# Strobe_blank.net
KiCad netlist of a schematic drawn in EAGLE
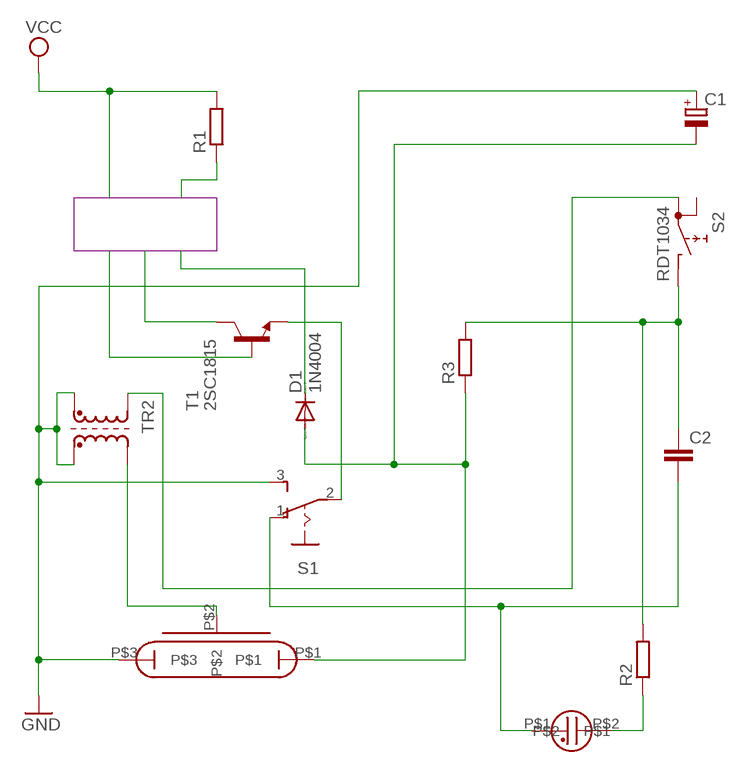
[diagram p0: schematic, sheet 1]

(export (version "E")
  (design (tool "Eeschema 10.0.6"))
  (components
    (comp (ref "C1")
      (value "CPOL-EU140CLH-0810")
      (footprint "eagle-import:140CLH-0810")
      (libsource (lib "eagle-import") (part "CPOL-EU140CLH-0810"))
    )
    (comp (ref "C2")
      (value "C-EU150-054X183")
      (footprint "eagle-import:C150-054X183")
      (libsource (lib "eagle-import") (part "C-EU150-054X183"))
    )
    (comp (ref "D1")
      (value "1N4004")
      (footprint "eagle-import:DO41-10")
      (libsource (lib "eagle-import") (part "1N4004"))
    )
    (comp (ref "R1")
      (value "R-EU_0204/2V")
      (footprint "eagle-import:0204V")
      (libsource (lib "eagle-import") (part "R-EU_0204/2V"))
    )
    (comp (ref "R2")
      (value "R-EU_0204/2V")
      (footprint "eagle-import:0204V")
      (libsource (lib "eagle-import") (part "R-EU_0204/2V"))
    )
    (comp (ref "R3")
      (value "R-EU_0204/2V")
      (footprint "eagle-import:0204V")
      (libsource (lib "eagle-import") (part "R-EU_0204/2V"))
    )
    (comp (ref "S1")
      (value "255SB")
      (footprint "eagle-import:255SB")
      (libsource (lib "eagle-import") (part "255SB"))
    )
    (comp (ref "S2")
      (value "RDT1034")
      (footprint "eagle-import:RDT1034")
      (libsource (lib "eagle-import") (part "RDT1034"))
    )
    (comp (ref "T1")
      (value "2SC1815")
      (footprint "eagle-import:TO92-ECB")
      (libsource (lib "eagle-import") (part "2SC1815"))
    )
    (comp (ref "TR2")
      (value "SM-T4")
      (footprint "eagle-import:SM-T4")
      (libsource (lib "eagle-import") (part "SM-T4"))
    )
    (comp (ref "U$1")
      (value "XENON")
      (footprint "eagle-import:XENON")
      (libsource (lib "eagle-import") (part "XENON"))
    )
    (comp (ref "U$2")
      (value "NEON")
      (footprint "eagle-import:NEON")
      (libsource (lib "eagle-import") (part "NEON"))
    )
  )
  (nets
    (net (code "1") (name "GND") (class "Default")
      (node (ref "C1") (pin "+") (pinfunction "+_+") (pintype "passive"))
      (node (ref "S1") (pin "3") (pinfunction "S_3") (pintype "passive"))
      (node (ref "TR2") (pin "2") (pinfunction "E1_2") (pintype "passive"))
      (node (ref "TR2") (pin "4") (pinfunction "E2_4") (pintype "passive"))
      (node (ref "U$1") (pin "P$3") (pinfunction "P$3_P$3") (pintype "bidirectional"))
    )
    (net (code "2") (name "Net-(C1-Pad-)") (class "Default")
      (node (ref "C1") (pin "-") (pinfunction "-_-") (pintype "passive"))
      (node (ref "D1") (pin "A") (pinfunction "A_A") (pintype "passive"))
      (node (ref "R3") (pin "1") (pinfunction "1_1") (pintype "passive"))
      (node (ref "U$1") (pin "P$1") (pinfunction "P$1_P$1") (pintype "bidirectional"))
    )
    (net (code "3") (name "Net-(C2-Pad1)") (class "Default")
      (node (ref "C2") (pin "1") (pinfunction "1_1") (pintype "passive"))
      (node (ref "R2") (pin "2") (pinfunction "2_2") (pintype "passive"))
      (node (ref "R3") (pin "2") (pinfunction "2_2") (pintype "passive"))
      (node (ref "S2") (pin "B") (pinfunction "B_B") (pintype "passive"))
    )
    (net (code "4") (name "Net-(R2-Pad1)") (class "Default")
      (node (ref "R2") (pin "1") (pinfunction "1_1") (pintype "passive"))
      (node (ref "U$2") (pin "P$2") (pinfunction "P$2_P$2") (pintype "bidirectional"))
    )
    (net (code "5") (name "Net-(S1-O)") (class "Default")
      (node (ref "C2") (pin "2") (pinfunction "2_2") (pintype "passive"))
      (node (ref "S1") (pin "1") (pinfunction "O_1") (pintype "passive"))
      (node (ref "U$2") (pin "P$1") (pinfunction "P$1_P$1") (pintype "bidirectional"))
    )
    (net (code "6") (name "Net-(S1-P)") (class "Default")
      (node (ref "S1") (pin "2") (pinfunction "P_2") (pintype "passive"))
      (node (ref "T1") (pin "E") (pinfunction "E_E") (pintype "passive"))
    )
    (net (code "7") (name "Net-(TR2-A1)") (class "Default")
      (node (ref "S2") (pin "A1") (pinfunction "A1_A1") (pintype "passive"))
      (node (ref "TR2") (pin "1") (pinfunction "A1_1") (pintype "passive"))
    )
    (net (code "8") (name "Net-(TR2-A2)") (class "Default")
      (node (ref "TR2") (pin "5") (pinfunction "A2_5") (pintype "passive"))
      (node (ref "U$1") (pin "P$2") (pinfunction "P$2_P$2") (pintype "bidirectional"))
    )
    (net (code "9") (name "VCC") (class "Default")
      (node (ref "R1") (pin "2") (pinfunction "2_2") (pintype "passive"))
    )
    (net (code "10") (name "unconnected-(D1-PadC)") (class "Default")
      (node (ref "D1") (pin "C") (pinfunction "C_C") (pintype "passive"))
    )
    (net (code "11") (name "unconnected-(R1-Pad1)") (class "Default")
      (node (ref "R1") (pin "1") (pinfunction "1_1") (pintype "passive"))
    )
    (net (code "12") (name "unconnected-(S2-PadA)") (class "Default")
      (node (ref "S2") (pin "A") (pinfunction "A_A") (pintype "passive"))
    )
    (net (code "13") (name "unconnected-(T1-PadB)") (class "Default")
      (node (ref "T1") (pin "B") (pinfunction "B_B") (pintype "passive"))
    )
    (net (code "14") (name "unconnected-(T1-PadC)") (class "Default")
      (node (ref "T1") (pin "C") (pinfunction "C_C") (pintype "passive"))
    )
  )
)
